# 10_POWER.net
KiCad netlist of a schematic drawn in Altium Designer
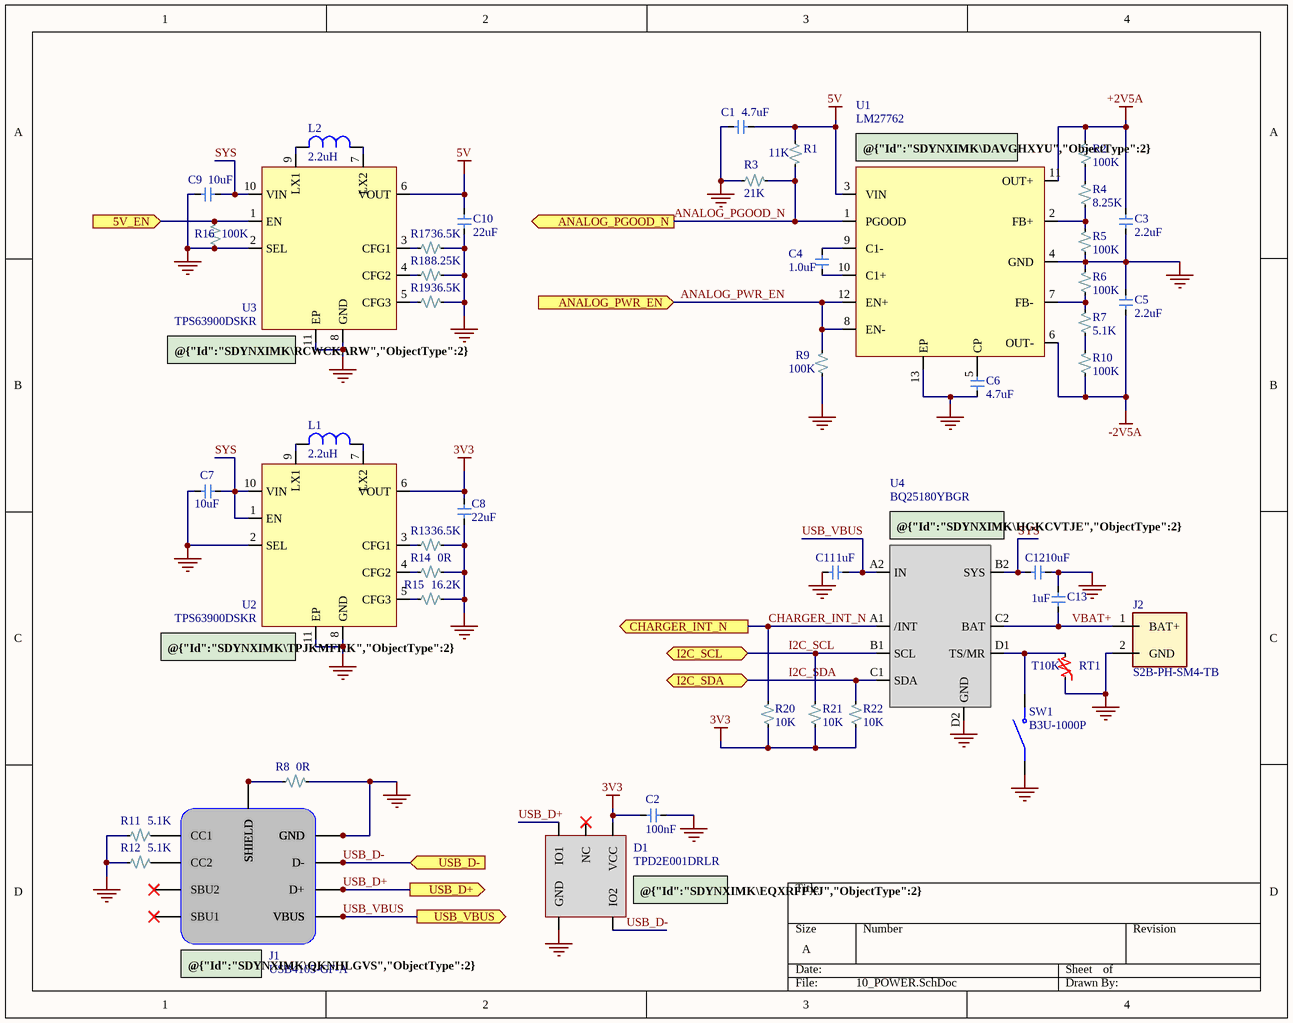
[diagram p0: 10_POWER.SchDoc]

(export (version "E")
  (design (tool "Eeschema 10.0.6"))
  (components
    (comp (ref "C1")
      (value "4.7uF")
      (footprint "C0805")
      (libsource (lib "PocketLab_DMM_SchLib") (part "C_0805"))
    )
    (comp (ref "C2")
      (value "100nF")
      (footprint "C0805")
      (libsource (lib "PocketLab_DMM_SchLib") (part "C_0805"))
    )
    (comp (ref "C3")
      (value "2.2uF")
      (footprint "C0805")
      (libsource (lib "PocketLab_DMM_SchLib") (part "C_0805"))
    )
    (comp (ref "C4")
      (value "1.0uF")
      (footprint "C0805")
      (libsource (lib "PocketLab_DMM_SchLib") (part "C_0805"))
    )
    (comp (ref "C5")
      (value "2.2uF")
      (footprint "C0805")
      (libsource (lib "PocketLab_DMM_SchLib") (part "C_0805"))
    )
    (comp (ref "C6")
      (value "4.7uF")
      (footprint "C0805")
      (libsource (lib "PocketLab_DMM_SchLib") (part "C_0805"))
    )
    (comp (ref "C7")
      (value "10uF")
      (footprint "C0805")
      (libsource (lib "PocketLab_DMM_SchLib") (part "C_0805"))
    )
    (comp (ref "C8")
      (value "22uF")
      (footprint "C0805")
      (libsource (lib "PocketLab_DMM_SchLib") (part "C_0805"))
    )
    (comp (ref "C9")
      (value "10uF")
      (footprint "C0805")
      (libsource (lib "PocketLab_DMM_SchLib") (part "C_0805"))
    )
    (comp (ref "C10")
      (value "22uF")
      (footprint "C0805")
      (libsource (lib "PocketLab_DMM_SchLib") (part "C_0805"))
    )
    (comp (ref "C11")
      (value "1uF")
      (footprint "C0805")
      (libsource (lib "PocketLab_DMM_SchLib") (part "C_0805"))
    )
    (comp (ref "C12")
      (value "10uF")
      (footprint "C0805")
      (libsource (lib "PocketLab_DMM_SchLib") (part "C_0805"))
    )
    (comp (ref "C13")
      (value "1uF")
      (footprint "C0805")
      (libsource (lib "PocketLab_DMM_SchLib") (part "C_0805"))
    )
    (comp (ref "D1")
      (value "TPD2E001DRLR")
      (footprint "TPD2E001DRLR")
      (description "TVS DIODE 5.5VWM SOT5")
      (fields (field (name "MANUFACTURER") "Texas Instruments"))
      (libsource (lib "PocketLab_DMM_EVT0") (part "TPD2E001DRLR"))
    )
    (comp (ref "J1")
      (value "USB4105-GF-A")
      (footprint "USB4105-GF-A")
      (description "USB Connector, 24 Contact(s), Female, Right Angle, Solder Terminal, Locking, Receptacle")
      (fields (field (name "MANUFACTURER") "Global Connector Technology"))
      (libsource (lib "PocketLab_DMM_SchLib") (part "USB4105-GF-A"))
    )
    (comp (ref "J2")
      (value "S2B-PH-SM4-TB")
      (footprint "S2B-PH-SM4-TB")
      (description "Board Connector, 2 Contact(s), 1 Row(s), Male, Right Angle, Surface Mount Terminal")
      (fields (field (name "MANUFACTURER") "JST"))
      (libsource (lib "PocketLab_DMM_SchLib") (part "S2B-PH-SM4-TB"))
    )
    (comp (ref "L1")
      (value "2.2uH")
      (footprint "WE_PMCI_201210")
      (description "FIXED IND 2.2UH 2A 190 MOHM SMD")
      (fields
        (field (name "MANUFACTURER") "Wurth Elektronik")
        (field (name "MANUFACTURER PART NUMBER") "74479275222")
      )
      (libsource (lib "PocketLab_DMM_EVT0") (part "74479275222"))
    )
    (comp (ref "L2")
      (value "2.2uH")
      (footprint "WE_PMCI_201210")
      (description "FIXED IND 2.2UH 2A 190 MOHM SMD")
      (fields
        (field (name "MANUFACTURER") "Wurth Elektronik")
        (field (name "MANUFACTURER PART NUMBER") "74479275222")
      )
      (libsource (lib "PocketLab_DMM_EVT0") (part "74479275222"))
    )
    (comp (ref "R1")
      (value "11K")
      (footprint "R0805")
      (description "RES 1/8W 0805")
      (fields
        (field (name "MANUFACTURER") "Stackpole Electronics")
        (field (name "MANUFACTURER PART NUMBER") "RNCF0805TKY10K0")
      )
      (libsource (lib "PocketLab_DMM_SchLib") (part "R_0805"))
    )
    (comp (ref "R2")
      (value "100K")
      (footprint "R0805")
      (description "RES 1/8W 0805")
      (fields
        (field (name "MANUFACTURER") "Stackpole Electronics")
        (field (name "MANUFACTURER PART NUMBER") "RNCF0805TKY10K0")
      )
      (libsource (lib "PocketLab_DMM_SchLib") (part "R_0805"))
    )
    (comp (ref "R3")
      (value "21K")
      (footprint "R0805")
      (description "RES 1/8W 0805")
      (fields
        (field (name "MANUFACTURER") "Stackpole Electronics")
        (field (name "MANUFACTURER PART NUMBER") "RNCF0805TKY10K0")
      )
      (libsource (lib "PocketLab_DMM_SchLib") (part "R_0805"))
    )
    (comp (ref "R4")
      (value "8.25K")
      (footprint "R0805")
      (description "RES 1/8W 0805")
      (fields
        (field (name "MANUFACTURER") "Stackpole Electronics")
        (field (name "MANUFACTURER PART NUMBER") "RNCF0805TKY10K0")
      )
      (libsource (lib "PocketLab_DMM_SchLib") (part "R_0805"))
    )
    (comp (ref "R5")
      (value "100K")
      (footprint "R0805")
      (description "RES 1/8W 0805")
      (fields
        (field (name "MANUFACTURER") "Stackpole Electronics")
        (field (name "MANUFACTURER PART NUMBER") "RNCF0805TKY10K0")
      )
      (libsource (lib "PocketLab_DMM_SchLib") (part "R_0805"))
    )
    (comp (ref "R6")
      (value "100K")
      (footprint "R0805")
      (description "RES 1/8W 0805")
      (fields
        (field (name "MANUFACTURER") "Stackpole Electronics")
        (field (name "MANUFACTURER PART NUMBER") "RNCF0805TKY10K0")
      )
      (libsource (lib "PocketLab_DMM_SchLib") (part "R_0805"))
    )
    (comp (ref "R7")
      (value "5.1K")
      (footprint "R0805")
      (description "RES 1/8W 0805")
      (fields
        (field (name "MANUFACTURER") "Stackpole Electronics")
        (field (name "MANUFACTURER PART NUMBER") "RNCF0805TKY10K0")
      )
      (libsource (lib "PocketLab_DMM_SchLib") (part "R_0805"))
    )
    (comp (ref "R8")
      (value "0R")
      (footprint "R0805")
      (description "RES 1/8W 0805")
      (fields
        (field (name "MANUFACTURER") "Stackpole Electronics")
        (field (name "MANUFACTURER PART NUMBER") "RNCF0805TKY10K0")
      )
      (libsource (lib "PocketLab_DMM_SchLib") (part "R_0805"))
    )
    (comp (ref "R9")
      (value "100K")
      (footprint "R0805")
      (description "RES 1/8W 0805")
      (fields
        (field (name "MANUFACTURER") "Stackpole Electronics")
        (field (name "MANUFACTURER PART NUMBER") "RNCF0805TKY10K0")
      )
      (libsource (lib "PocketLab_DMM_SchLib") (part "R_0805"))
    )
    (comp (ref "R10")
      (value "100K")
      (footprint "R0805")
      (description "RES 1/8W 0805")
      (fields
        (field (name "MANUFACTURER") "Stackpole Electronics")
        (field (name "MANUFACTURER PART NUMBER") "RNCF0805TKY10K0")
      )
      (libsource (lib "PocketLab_DMM_SchLib") (part "R_0805"))
    )
    (comp (ref "R11")
      (value "5.1K")
      (footprint "R0805")
      (description "RES 1/8W 0805")
      (fields
        (field (name "MANUFACTURER") "Stackpole Electronics")
        (field (name "MANUFACTURER PART NUMBER") "RNCF0805TKY10K0")
      )
      (libsource (lib "PocketLab_DMM_SchLib") (part "R_0805"))
    )
    (comp (ref "R12")
      (value "5.1K")
      (footprint "R0805")
      (description "RES 1/8W 0805")
      (fields
        (field (name "MANUFACTURER") "Stackpole Electronics")
        (field (name "MANUFACTURER PART NUMBER") "RNCF0805TKY10K0")
      )
      (libsource (lib "PocketLab_DMM_SchLib") (part "R_0805"))
    )
    (comp (ref "R13")
      (value "36.5K")
      (footprint "R0805")
      (description "RES 1/8W 0805")
      (fields
        (field (name "MANUFACTURER") "Stackpole Electronics")
        (field (name "MANUFACTURER PART NUMBER") "RNCF0805TKY10K0")
      )
      (libsource (lib "PocketLab_DMM_SchLib") (part "R_0805"))
    )
    (comp (ref "R14")
      (value "0R")
      (footprint "R0805")
      (description "RES 1/8W 0805")
      (fields
        (field (name "MANUFACTURER") "Stackpole Electronics")
        (field (name "MANUFACTURER PART NUMBER") "RNCF0805TKY10K0")
      )
      (libsource (lib "PocketLab_DMM_SchLib") (part "R_0805"))
    )
    (comp (ref "R15")
      (value "16.2K")
      (footprint "R0805")
      (description "RES 1/8W 0805")
      (fields
        (field (name "MANUFACTURER") "Stackpole Electronics")
        (field (name "MANUFACTURER PART NUMBER") "RNCF0805TKY10K0")
      )
      (libsource (lib "PocketLab_DMM_SchLib") (part "R_0805"))
    )
    (comp (ref "R16")
      (value "100K")
      (footprint "R0805")
      (description "RES 1/8W 0805")
      (fields
        (field (name "MANUFACTURER") "Stackpole Electronics")
        (field (name "MANUFACTURER PART NUMBER") "RNCF0805TKY10K0")
      )
      (libsource (lib "PocketLab_DMM_SchLib") (part "R_0805"))
    )
    (comp (ref "R17")
      (value "36.5K")
      (footprint "R0805")
      (description "RES 1/8W 0805")
      (fields
        (field (name "MANUFACTURER") "Stackpole Electronics")
        (field (name "MANUFACTURER PART NUMBER") "RNCF0805TKY10K0")
      )
      (libsource (lib "PocketLab_DMM_SchLib") (part "R_0805"))
    )
    (comp (ref "R18")
      (value "8.25K")
      (footprint "R0805")
      (description "RES 1/8W 0805")
      (fields
        (field (name "MANUFACTURER") "Stackpole Electronics")
        (field (name "MANUFACTURER PART NUMBER") "RNCF0805TKY10K0")
      )
      (libsource (lib "PocketLab_DMM_SchLib") (part "R_0805"))
    )
    (comp (ref "R19")
      (value "36.5K")
      (footprint "R0805")
      (description "RES 1/8W 0805")
      (fields
        (field (name "MANUFACTURER") "Stackpole Electronics")
        (field (name "MANUFACTURER PART NUMBER") "RNCF0805TKY10K0")
      )
      (libsource (lib "PocketLab_DMM_SchLib") (part "R_0805"))
    )
    (comp (ref "R20")
      (value "10K")
      (footprint "R0805")
      (description "RES 1/8W 0805")
      (fields
        (field (name "MANUFACTURER") "Stackpole Electronics")
        (field (name "MANUFACTURER PART NUMBER") "RNCF0805TKY10K0")
      )
      (libsource (lib "PocketLab_DMM_SchLib") (part "R_0805"))
    )
    (comp (ref "R21")
      (value "10K")
      (footprint "R0805")
      (description "RES 1/8W 0805")
      (fields
        (field (name "MANUFACTURER") "Stackpole Electronics")
        (field (name "MANUFACTURER PART NUMBER") "RNCF0805TKY10K0")
      )
      (libsource (lib "PocketLab_DMM_SchLib") (part "R_0805"))
    )
    (comp (ref "R22")
      (value "10K")
      (footprint "R0805")
      (description "RES 1/8W 0805")
      (fields
        (field (name "MANUFACTURER") "Stackpole Electronics")
        (field (name "MANUFACTURER PART NUMBER") "RNCF0805TKY10K0")
      )
      (libsource (lib "PocketLab_DMM_SchLib") (part "R_0805"))
    )
    (comp (ref "RT1")
      (value "T10K")
      (footprint "NCU18_1608")
      (description "THERMISTOR NTC 10KOHM 3380K 0603 / NTC Thermistor 10k 0603 (1608 Metric)")
      (fields
        (field (name "MANUFACTURER") "Murata")
        (field (name "MANUFACTURER PART NUMBER") "NCU18XH103F6SRB")
      )
      (libsource (lib "PocketLab_DMM_EVT0") (part "NCU18XH103F6SRB"))
    )
    (comp (ref "SW1")
      (value "B3U-1000P")
      (footprint "B3U-1000P")
      (description "Switch Tactile N.O. SPST Round Button Solder Tab 12VDC 200000Cycles 1.5N SMD Emboss T/R")
      (fields (field (name "MANUFACTURER") "Omron"))
      (libsource (lib "PocketLab_DMM_SchLib") (part "B3U-1000P"))
    )
    (comp (ref "U1")
      (value "LM27762")
      (footprint "LM27762")
      (description "IC REG CHARGE PUMP ADJ DL 12WSON")
      (fields
        (field (name "MANUFACTURER") "Texas Instruments")
        (field (name "MANUFACTURER PART NUMBER") "LM27762DSSR")
      )
      (libsource (lib "PocketLab_DMM_EVT0") (part "LM27762DSSR"))
    )
    (comp (ref "U2")
      (value "TPS63900DSKR")
      (footprint "TPS63900")
      (description "Buck-Boost Yes 2MHz Programmable 1 5V 1.8V 5.5V 1.8V WFDFN-10(EP) SMD mount，glue mount")
      (fields (field (name "MANUFACTURER") "Texas Instruments"))
      (libsource (lib "PocketLab_DMM_SchLib") (part "TPS63900DSKR"))
    )
    (comp (ref "U3")
      (value "TPS63900DSKR")
      (footprint "TPS63900")
      (description "Buck-Boost Yes 2MHz Programmable 1 5V 1.8V 5.5V 1.8V WFDFN-10(EP) SMD mount，glue mount")
      (fields (field (name "MANUFACTURER") "Texas Instruments"))
      (libsource (lib "PocketLab_DMM_SchLib") (part "TPS63900DSKR"))
    )
    (comp (ref "U4")
      (value "BQ25180YBGR")
      (footprint "BQ25180")
      (description "5.5V /Polymer 1 1A DSBGA-8(1.1x1.6) Battery Management ICs ROHS")
      (fields (field (name "MANUFACTURER") "Texas Instruments"))
      (libsource (lib "PocketLab_DMM_SchLib") (part "BQ25180YBGR"))
    )
  )
  (nets
    (net (code "1") (name "+2V5A") (class "Default")
      (node (ref "C3") (pin "2") (pinfunction "2_2") (pintype "passive"))
      (node (ref "R2") (pin "2") (pinfunction "2_2") (pintype "passive"))
      (node (ref "U1") (pin "11") (pinfunction "OUT+_11") (pintype "passive"))
    )
    (net (code "2") (name "-2V5A") (class "Default")
      (node (ref "C5") (pin "2") (pinfunction "2_2") (pintype "passive"))
      (node (ref "R10") (pin "1") (pinfunction "1_1") (pintype "passive"))
      (node (ref "U1") (pin "6") (pinfunction "OUT-_6") (pintype "passive"))
    )
    (net (code "3") (name "/5V_EN") (class "Default")
      (node (ref "R16") (pin "2") (pinfunction "2_2") (pintype "passive"))
      (node (ref "U3") (pin "1") (pinfunction "EN_1") (pintype "passive"))
    )
    (net (code "4") (name "/ANALOG_PGOOD_N") (class "Default")
      (node (ref "R1") (pin "2") (pinfunction "2_2") (pintype "passive"))
      (node (ref "R3") (pin "2") (pinfunction "2_2") (pintype "passive"))
      (node (ref "U1") (pin "1") (pinfunction "PGOOD_1") (pintype "passive"))
    )
    (net (code "5") (name "/ANALOG_PWR_EN") (class "Default")
      (node (ref "R9") (pin "2") (pinfunction "2_2") (pintype "passive"))
      (node (ref "U1") (pin "12") (pinfunction "EN+_12") (pintype "passive"))
      (node (ref "U1") (pin "8") (pinfunction "EN-_8") (pintype "passive"))
    )
    (net (code "6") (name "/CHARGER_INT_N") (class "Default")
      (node (ref "R20") (pin "2") (pinfunction "2_2") (pintype "passive"))
      (node (ref "U4") (pin "A1") (pinfunction "/INT_A1") (pintype "passive"))
    )
    (net (code "7") (name "/I2C_SCL") (class "Default")
      (node (ref "R21") (pin "2") (pinfunction "2_2") (pintype "passive"))
      (node (ref "U4") (pin "B1") (pinfunction "SCL_B1") (pintype "passive"))
    )
    (net (code "8") (name "/I2C_SDA") (class "Default")
      (node (ref "R22") (pin "2") (pinfunction "2_2") (pintype "passive"))
      (node (ref "U4") (pin "C1") (pinfunction "SDA_C1") (pintype "passive"))
    )
    (net (code "9") (name "/SYS") (class "Default")
      (node (ref "C12") (pin "1") (pinfunction "1_1") (pintype "passive"))
      (node (ref "C7") (pin "1") (pinfunction "1_1") (pintype "passive"))
      (node (ref "C9") (pin "1") (pinfunction "1_1") (pintype "passive"))
      (node (ref "U2") (pin "1") (pinfunction "EN_1") (pintype "passive"))
      (node (ref "U2") (pin "10") (pinfunction "VIN_10") (pintype "passive"))
      (node (ref "U3") (pin "10") (pinfunction "VIN_10") (pintype "passive"))
      (node (ref "U4") (pin "B2") (pinfunction "SYS_B2") (pintype "passive"))
    )
    (net (code "10") (name "/USB_D+") (class "Default")
      (node (ref "D1") (pin "3") (pinfunction "IO1_3") (pintype "passive"))
      (node (ref "J1") (pin "A6") (pinfunction "D+_A6") (pintype "passive"))
      (node (ref "J1") (pin "B6") (pinfunction "D+_B6") (pintype "passive"))
    )
    (net (code "11") (name "/USB_D-") (class "Default")
      (node (ref "D1") (pin "5") (pinfunction "IO2_5") (pintype "passive"))
      (node (ref "J1") (pin "A7") (pinfunction "D-_A7") (pintype "passive"))
      (node (ref "J1") (pin "B7") (pinfunction "D-_B7") (pintype "passive"))
    )
    (net (code "12") (name "/USB_VBUS") (class "Default")
      (node (ref "C11") (pin "1") (pinfunction "1_1") (pintype "passive"))
      (node (ref "J1") (pin "A4") (pinfunction "VBUS_A4") (pintype "passive"))
      (node (ref "J1") (pin "A9") (pinfunction "VBUS_A9") (pintype "passive"))
      (node (ref "J1") (pin "B4") (pinfunction "VBUS_B4") (pintype "passive"))
      (node (ref "J1") (pin "B9") (pinfunction "VBUS_B9") (pintype "passive"))
      (node (ref "U4") (pin "A2") (pinfunction "IN_A2") (pintype "passive"))
    )
    (net (code "13") (name "/VBAT+") (class "Default")
      (node (ref "C13") (pin "1") (pinfunction "1_1") (pintype "passive"))
      (node (ref "J2") (pin "1") (pinfunction "BAT+_1") (pintype "passive"))
      (node (ref "U4") (pin "C2") (pinfunction "BAT_C2") (pintype "passive"))
    )
    (net (code "14") (name "3V3") (class "Default")
      (node (ref "C2") (pin "1") (pinfunction "1_1") (pintype "passive"))
      (node (ref "C8") (pin "2") (pinfunction "2_2") (pintype "passive"))
      (node (ref "D1") (pin "1") (pinfunction "VCC_1") (pintype "passive"))
      (node (ref "R20") (pin "1") (pinfunction "1_1") (pintype "passive"))
      (node (ref "R21") (pin "1") (pinfunction "1_1") (pintype "passive"))
      (node (ref "R22") (pin "1") (pinfunction "1_1") (pintype "passive"))
      (node (ref "U2") (pin "6") (pinfunction "VOUT_6") (pintype "passive"))
    )
    (net (code "15") (name "5V") (class "Default")
      (node (ref "C1") (pin "1") (pinfunction "1_1") (pintype "passive"))
      (node (ref "C10") (pin "2") (pinfunction "2_2") (pintype "passive"))
      (node (ref "R1") (pin "1") (pinfunction "1_1") (pintype "passive"))
      (node (ref "U1") (pin "3") (pinfunction "VIN_3") (pintype "passive"))
      (node (ref "U3") (pin "6") (pinfunction "VOUT_6") (pintype "passive"))
    )
    (net (code "16") (name "GND") (class "Default")
      (node (ref "C1") (pin "2") (pinfunction "2_2") (pintype "passive"))
      (node (ref "C10") (pin "1") (pinfunction "1_1") (pintype "passive"))
      (node (ref "C11") (pin "2") (pinfunction "2_2") (pintype "passive"))
      (node (ref "C12") (pin "2") (pinfunction "2_2") (pintype "passive"))
      (node (ref "C13") (pin "2") (pinfunction "2_2") (pintype "passive"))
      (node (ref "C2") (pin "2") (pinfunction "2_2") (pintype "passive"))
      (node (ref "C3") (pin "1") (pinfunction "1_1") (pintype "passive"))
      (node (ref "C5") (pin "1") (pinfunction "1_1") (pintype "passive"))
      (node (ref "C6") (pin "1") (pinfunction "1_1") (pintype "passive"))
      (node (ref "C7") (pin "2") (pinfunction "2_2") (pintype "passive"))
      (node (ref "C8") (pin "1") (pinfunction "1_1") (pintype "passive"))
      (node (ref "C9") (pin "2") (pinfunction "2_2") (pintype "passive"))
      (node (ref "D1") (pin "4") (pinfunction "GND_4") (pintype "passive"))
      (node (ref "J1") (pin "A1") (pinfunction "GND_A1") (pintype "passive"))
      (node (ref "J1") (pin "A12") (pinfunction "GND_A12") (pintype "passive"))
      (node (ref "J1") (pin "B1") (pinfunction "GND_B1") (pintype "passive"))
      (node (ref "J1") (pin "B12") (pinfunction "GND_B12") (pintype "passive"))
      (node (ref "J2") (pin "2") (pinfunction "GND_2") (pintype "passive"))
      (node (ref "R11") (pin "1") (pinfunction "1_1") (pintype "passive"))
      (node (ref "R12") (pin "1") (pinfunction "1_1") (pintype "passive"))
      (node (ref "R13") (pin "2") (pinfunction "2_2") (pintype "passive"))
      (node (ref "R14") (pin "2") (pinfunction "2_2") (pintype "passive"))
      (node (ref "R15") (pin "2") (pinfunction "2_2") (pintype "passive"))
      (node (ref "R16") (pin "1") (pinfunction "1_1") (pintype "passive"))
      (node (ref "R17") (pin "2") (pinfunction "2_2") (pintype "passive"))
      (node (ref "R18") (pin "2") (pinfunction "2_2") (pintype "passive"))
      (node (ref "R19") (pin "2") (pinfunction "2_2") (pintype "passive"))
      (node (ref "R3") (pin "1") (pinfunction "1_1") (pintype "passive"))
      (node (ref "R5") (pin "1") (pinfunction "1_1") (pintype "passive"))
      (node (ref "R6") (pin "2") (pinfunction "2_2") (pintype "passive"))
      (node (ref "R8") (pin "2") (pinfunction "2_2") (pintype "passive"))
      (node (ref "R9") (pin "1") (pinfunction "1_1") (pintype "passive"))
      (node (ref "RT1") (pin "1") (pinfunction "1_1") (pintype "passive"))
      (node (ref "SW1") (pin "1") (pinfunction "1_1") (pintype "passive"))
      (node (ref "U1") (pin "13") (pinfunction "EP_13") (pintype "passive"))
      (node (ref "U1") (pin "4") (pinfunction "GND_4") (pintype "passive"))
      (node (ref "U2") (pin "11") (pinfunction "EP_11") (pintype "passive"))
      (node (ref "U2") (pin "2") (pinfunction "SEL_2") (pintype "passive"))
      (node (ref "U2") (pin "8") (pinfunction "GND_8") (pintype "passive"))
      (node (ref "U3") (pin "11") (pinfunction "EP_11") (pintype "passive"))
      (node (ref "U3") (pin "2") (pinfunction "SEL_2") (pintype "passive"))
      (node (ref "U3") (pin "8") (pinfunction "GND_8") (pintype "passive"))
      (node (ref "U4") (pin "D2") (pinfunction "GND_D2") (pintype "passive"))
    )
    (net (code "17") (name "Net-(J1-CC1)") (class "Default")
      (node (ref "J1") (pin "A5") (pinfunction "CC1_A5") (pintype "passive"))
      (node (ref "R11") (pin "2") (pinfunction "2_2") (pintype "passive"))
    )
    (net (code "18") (name "Net-(J1-CC2)") (class "Default")
      (node (ref "J1") (pin "B5") (pinfunction "CC2_B5") (pintype "passive"))
      (node (ref "R12") (pin "2") (pinfunction "2_2") (pintype "passive"))
    )
    (net (code "19") (name "Net-(J1-SHIELD-PadSHIELD1)") (class "Default")
      (node (ref "J1") (pin "SHIELD1") (pinfunction "SHIELD_SHIELD1") (pintype "passive"))
      (node (ref "J1") (pin "SHIELD2") (pinfunction "SHIELD_SHIELD2") (pintype "passive"))
      (node (ref "J1") (pin "SHIELD3") (pinfunction "SHIELD_SHIELD3") (pintype "passive"))
      (node (ref "J1") (pin "SHIELD4") (pinfunction "SHIELD_SHIELD4") (pintype "passive"))
      (node (ref "R8") (pin "1") (pinfunction "1_1") (pintype "passive"))
    )
    (net (code "20") (name "Net-(R2-Pad1)") (class "Default")
      (node (ref "R2") (pin "1") (pinfunction "1_1") (pintype "passive"))
      (node (ref "R4") (pin "2") (pinfunction "2_2") (pintype "passive"))
    )
    (net (code "21") (name "Net-(R10-Pad2)") (class "Default")
      (node (ref "R10") (pin "2") (pinfunction "2_2") (pintype "passive"))
      (node (ref "R7") (pin "1") (pinfunction "1_1") (pintype "passive"))
    )
    (net (code "22") (name "Net-(U1-C1+)") (class "Default")
      (node (ref "C4") (pin "1") (pinfunction "1_1") (pintype "passive"))
      (node (ref "U1") (pin "10") (pinfunction "C1+_10") (pintype "passive"))
    )
    (net (code "23") (name "Net-(U1-C1-)") (class "Default")
      (node (ref "C4") (pin "2") (pinfunction "2_2") (pintype "passive"))
      (node (ref "U1") (pin "9") (pinfunction "C1-_9") (pintype "passive"))
    )
    (net (code "24") (name "Net-(U1-CP)") (class "Default")
      (node (ref "C6") (pin "2") (pinfunction "2_2") (pintype "passive"))
      (node (ref "U1") (pin "5") (pinfunction "CP_5") (pintype "passive"))
    )
    (net (code "25") (name "Net-(U1-FB+)") (class "Default")
      (node (ref "R4") (pin "1") (pinfunction "1_1") (pintype "passive"))
      (node (ref "R5") (pin "2") (pinfunction "2_2") (pintype "passive"))
      (node (ref "U1") (pin "2") (pinfunction "FB+_2") (pintype "passive"))
    )
    (net (code "26") (name "Net-(U1-FB-)") (class "Default")
      (node (ref "R6") (pin "1") (pinfunction "1_1") (pintype "passive"))
      (node (ref "R7") (pin "2") (pinfunction "2_2") (pintype "passive"))
      (node (ref "U1") (pin "7") (pinfunction "FB-_7") (pintype "passive"))
    )
    (net (code "27") (name "Net-(U2-CFG1)") (class "Default")
      (node (ref "R13") (pin "1") (pinfunction "1_1") (pintype "passive"))
      (node (ref "U2") (pin "3") (pinfunction "CFG1_3") (pintype "passive"))
    )
    (net (code "28") (name "Net-(U2-CFG2)") (class "Default")
      (node (ref "R14") (pin "1") (pinfunction "1_1") (pintype "passive"))
      (node (ref "U2") (pin "4") (pinfunction "CFG2_4") (pintype "passive"))
    )
    (net (code "29") (name "Net-(U2-CFG3)") (class "Default")
      (node (ref "R15") (pin "1") (pinfunction "1_1") (pintype "passive"))
      (node (ref "U2") (pin "5") (pinfunction "CFG3_5") (pintype "passive"))
    )
    (net (code "30") (name "Net-(U2-LX1)") (class "Default")
      (node (ref "L1") (pin "1") (pinfunction "1_1") (pintype "passive"))
      (node (ref "U2") (pin "9") (pinfunction "LX1_9") (pintype "passive"))
    )
    (net (code "31") (name "Net-(U2-LX2)") (class "Default")
      (node (ref "L1") (pin "2") (pinfunction "2_2") (pintype "passive"))
      (node (ref "U2") (pin "7") (pinfunction "LX2_7") (pintype "passive"))
    )
    (net (code "32") (name "Net-(U3-CFG1)") (class "Default")
      (node (ref "R17") (pin "1") (pinfunction "1_1") (pintype "passive"))
      (node (ref "U3") (pin "3") (pinfunction "CFG1_3") (pintype "passive"))
    )
    (net (code "33") (name "Net-(U3-CFG2)") (class "Default")
      (node (ref "R18") (pin "1") (pinfunction "1_1") (pintype "passive"))
      (node (ref "U3") (pin "4") (pinfunction "CFG2_4") (pintype "passive"))
    )
    (net (code "34") (name "Net-(U3-CFG3)") (class "Default")
      (node (ref "R19") (pin "1") (pinfunction "1_1") (pintype "passive"))
      (node (ref "U3") (pin "5") (pinfunction "CFG3_5") (pintype "passive"))
    )
    (net (code "35") (name "Net-(U3-LX1)") (class "Default")
      (node (ref "L2") (pin "1") (pinfunction "1_1") (pintype "passive"))
      (node (ref "U3") (pin "9") (pinfunction "LX1_9") (pintype "passive"))
    )
    (net (code "36") (name "Net-(U3-LX2)") (class "Default")
      (node (ref "L2") (pin "2") (pinfunction "2_2") (pintype "passive"))
      (node (ref "U3") (pin "7") (pinfunction "LX2_7") (pintype "passive"))
    )
    (net (code "37") (name "Net-(U4-TS{slash}MR)") (class "Default")
      (node (ref "RT1") (pin "2") (pinfunction "2_2") (pintype "passive"))
      (node (ref "SW1") (pin "2") (pinfunction "2_2") (pintype "passive"))
      (node (ref "U4") (pin "D1") (pinfunction "TS/MR_D1") (pintype "passive"))
    )
    (net (code "38") (name "unconnected-(D1-NC-Pad2)") (class "Default")
      (node (ref "D1") (pin "2") (pinfunction "NC_2") (pintype "passive+no_connect"))
    )
    (net (code "39") (name "unconnected-(J1-SBU1-PadA8)") (class "Default")
      (node (ref "J1") (pin "A8") (pinfunction "SBU1_A8") (pintype "passive+no_connect"))
    )
    (net (code "40") (name "unconnected-(J1-SBU2-PadB8)") (class "Default")
      (node (ref "J1") (pin "B8") (pinfunction "SBU2_B8") (pintype "passive+no_connect"))
    )
  )
)
